# M2_NVME.net
KiCad netlist of a schematic drawn in Altium Designer
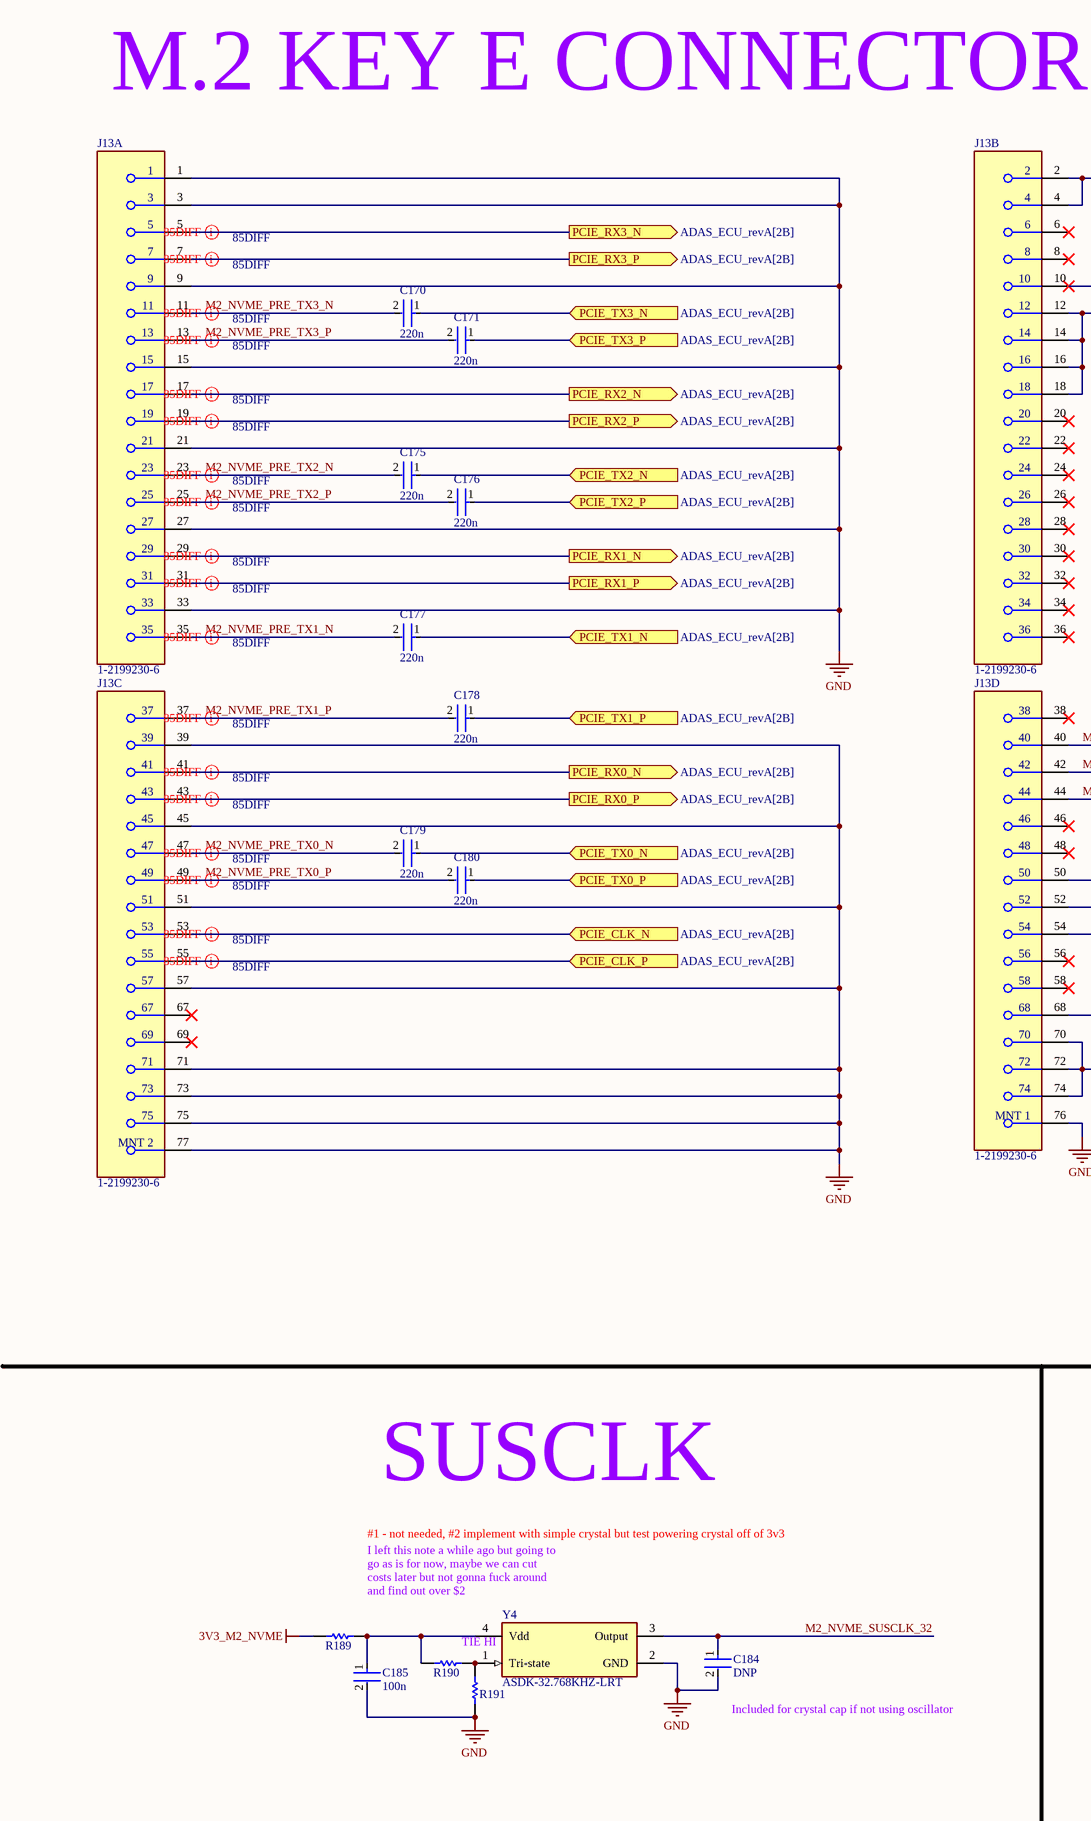
[diagram p0: M2_NVME.SchDoc, left]
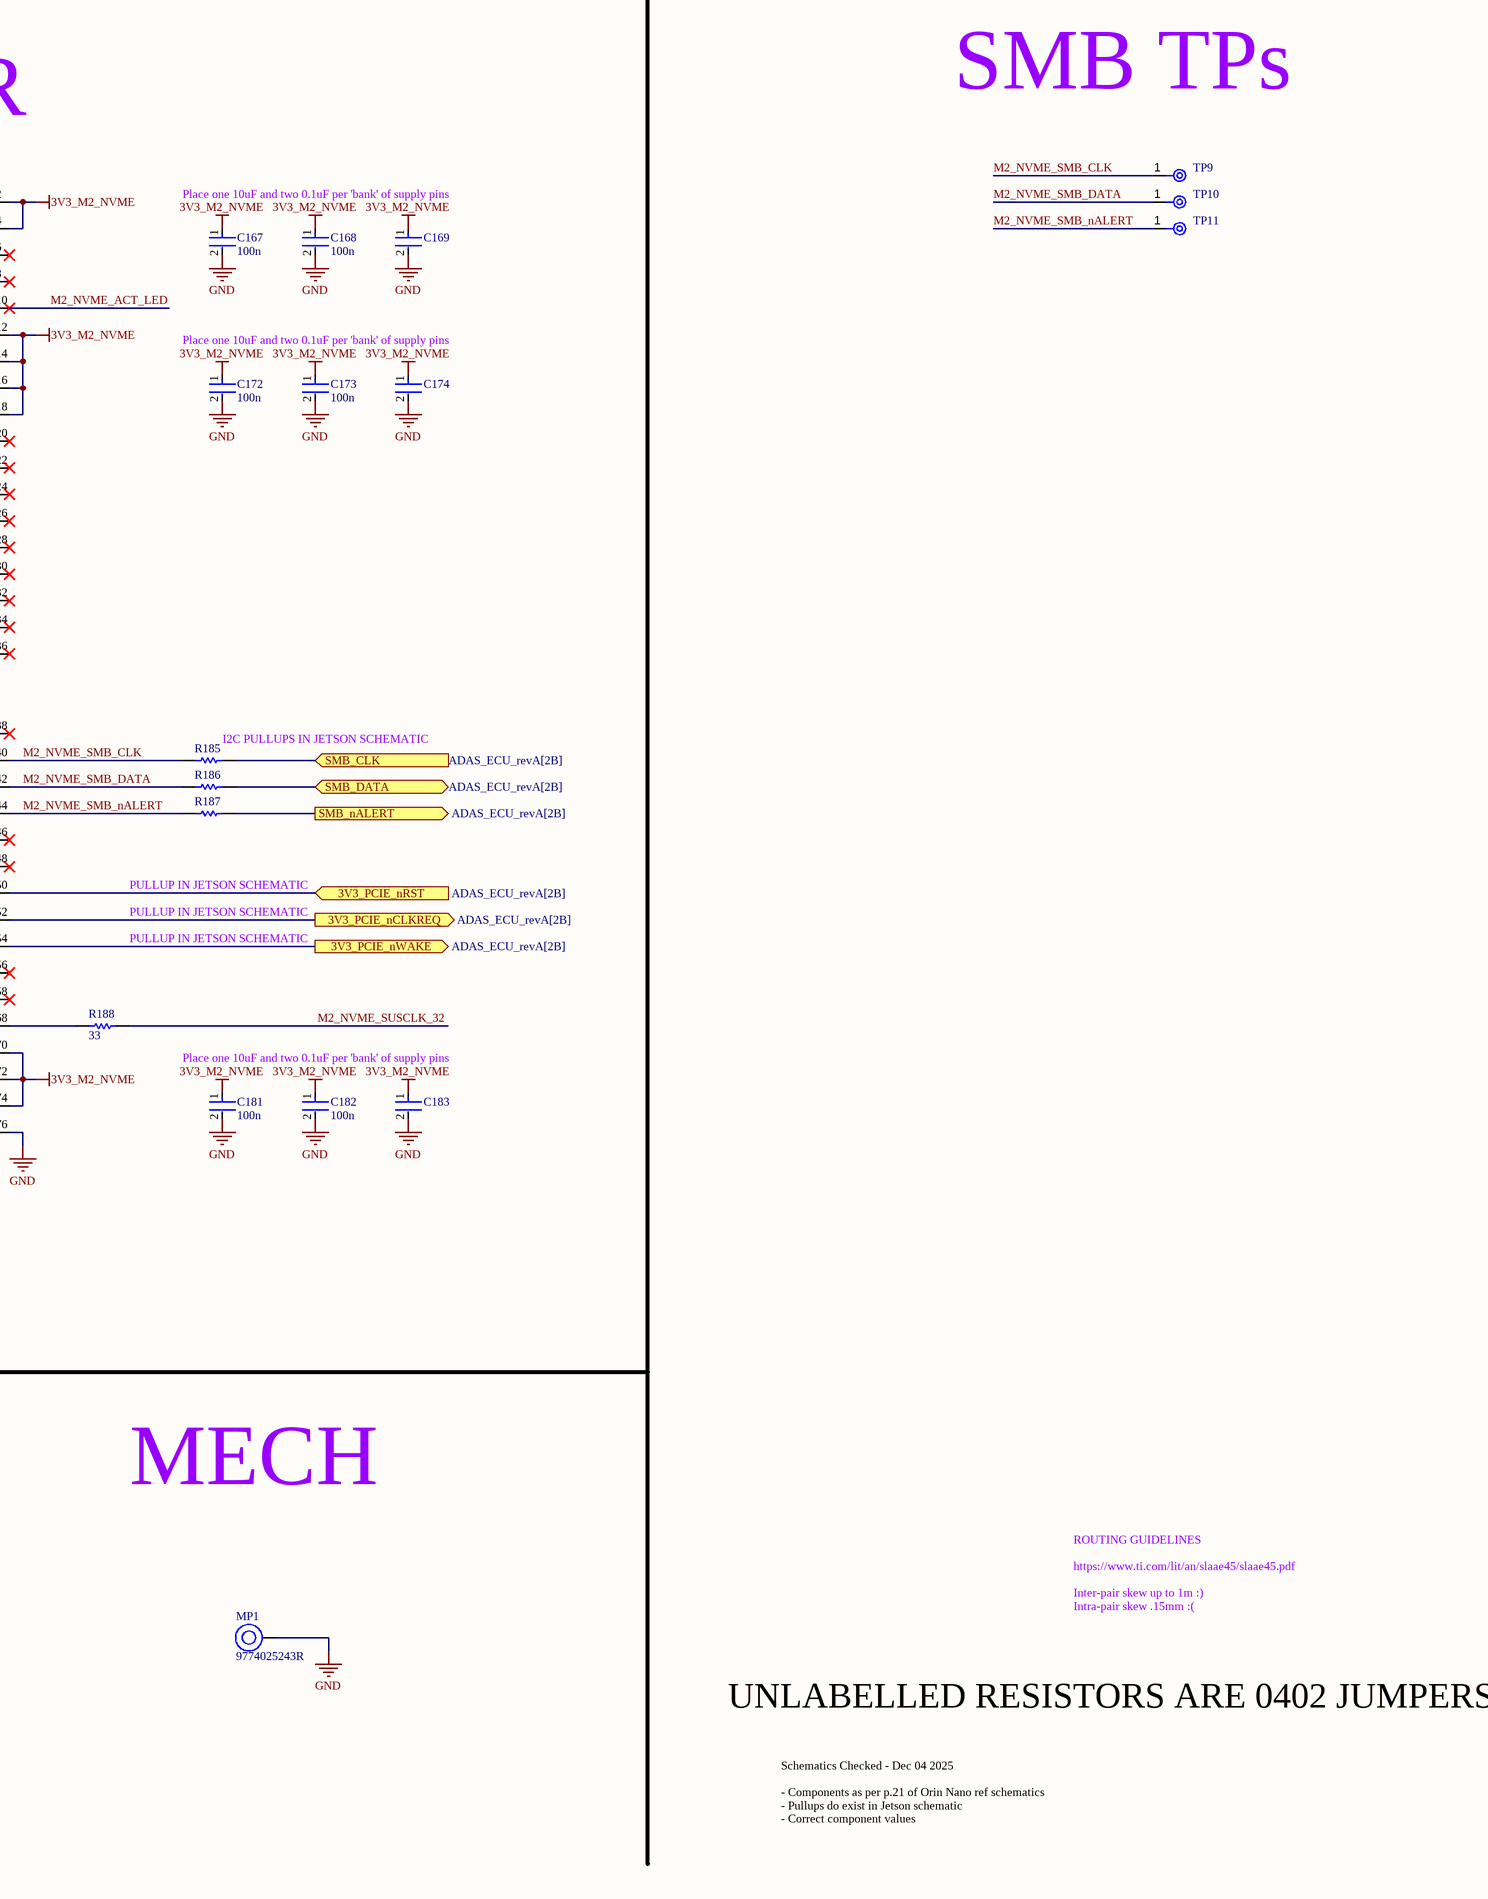
[diagram p1: M2_NVME.SchDoc, right]

(export (version "E")
  (design (tool "Eeschema 10.0.6"))
  (components
    (comp (ref "C167")
      (value "100n")
      (footprint "FP-0402-L_1_0_0_05-W_0_5-IPC_A")
      (description "LARGE PADS, 0402 CAP, CHANGE COMMENT TO MATCH REAL P/N")
      (libsource (lib "Space Concordia") (part "b4654b650e69147ec39a6b967a45e02"))
    )
    (comp (ref "C168")
      (value "100n")
      (footprint "FP-0402-L_1_0_0_05-W_0_5-IPC_A")
      (description "LARGE PADS, 0402 CAP, CHANGE COMMENT TO MATCH REAL P/N")
      (libsource (lib "Space Concordia") (part "b4654b650e69147ec39a6b967a45e02"))
    )
    (comp (ref "C169")
      (value "GRM188R60J106ME47D")
      (footprint "FP-GRM188-0_1-e0_2_0_55-IPC_A")
      (description "Chip Multilayer Ceramic Capacitors for General Purpose, 0603, 10uF, X5R, 15%, 20%, 6.3V")
      (fields (field (name "VOLTAGE") "6.3V") (field (name "TOLERANCE") "20%"))
      (libsource (lib "Altium Content Vault") (part "02cd4be3c70576c341d710602a673aa"))
    )
    (comp (ref "C170")
      (value "220n")
      (footprint "FP-0402-L_1_0_0_05-W_0_5-IPC_A")
      (description "LARGE PADS, 0402 CAP, CHANGE COMMENT TO MATCH REAL P/N")
      (libsource (lib "Space Concordia") (part "b4654b650e69147ec39a6b967a45e02"))
    )
    (comp (ref "C171")
      (value "220n")
      (footprint "FP-0402-L_1_0_0_05-W_0_5-IPC_A")
      (description "LARGE PADS, 0402 CAP, CHANGE COMMENT TO MATCH REAL P/N")
      (libsource (lib "Space Concordia") (part "b4654b650e69147ec39a6b967a45e02"))
    )
    (comp (ref "C172")
      (value "100n")
      (footprint "FP-0402-L_1_0_0_05-W_0_5-IPC_A")
      (description "LARGE PADS, 0402 CAP, CHANGE COMMENT TO MATCH REAL P/N")
      (libsource (lib "Space Concordia") (part "b4654b650e69147ec39a6b967a45e02"))
    )
    (comp (ref "C173")
      (value "100n")
      (footprint "FP-0402-L_1_0_0_05-W_0_5-IPC_A")
      (description "LARGE PADS, 0402 CAP, CHANGE COMMENT TO MATCH REAL P/N")
      (libsource (lib "Space Concordia") (part "b4654b650e69147ec39a6b967a45e02"))
    )
    (comp (ref "C174")
      (value "GRM188R60J106ME47D")
      (footprint "FP-GRM188-0_1-e0_2_0_55-IPC_A")
      (description "Chip Multilayer Ceramic Capacitors for General Purpose, 0603, 10uF, X5R, 15%, 20%, 6.3V")
      (fields (field (name "VOLTAGE") "6.3V") (field (name "TOLERANCE") "20%"))
      (libsource (lib "Altium Content Vault") (part "02cd4be3c70576c341d710602a673aa"))
    )
    (comp (ref "C175")
      (value "220n")
      (footprint "FP-0402-L_1_0_0_05-W_0_5-IPC_A")
      (description "LARGE PADS, 0402 CAP, CHANGE COMMENT TO MATCH REAL P/N")
      (libsource (lib "Space Concordia") (part "b4654b650e69147ec39a6b967a45e02"))
    )
    (comp (ref "C176")
      (value "220n")
      (footprint "FP-0402-L_1_0_0_05-W_0_5-IPC_A")
      (description "LARGE PADS, 0402 CAP, CHANGE COMMENT TO MATCH REAL P/N")
      (libsource (lib "Space Concordia") (part "b4654b650e69147ec39a6b967a45e02"))
    )
    (comp (ref "C177")
      (value "220n")
      (footprint "FP-0402-L_1_0_0_05-W_0_5-IPC_A")
      (description "LARGE PADS, 0402 CAP, CHANGE COMMENT TO MATCH REAL P/N")
      (libsource (lib "Space Concordia") (part "b4654b650e69147ec39a6b967a45e02"))
    )
    (comp (ref "C178")
      (value "220n")
      (footprint "FP-0402-L_1_0_0_05-W_0_5-IPC_A")
      (description "LARGE PADS, 0402 CAP, CHANGE COMMENT TO MATCH REAL P/N")
      (libsource (lib "Space Concordia") (part "b4654b650e69147ec39a6b967a45e02"))
    )
    (comp (ref "C179")
      (value "220n")
      (footprint "FP-0402-L_1_0_0_05-W_0_5-IPC_A")
      (description "LARGE PADS, 0402 CAP, CHANGE COMMENT TO MATCH REAL P/N")
      (libsource (lib "Space Concordia") (part "b4654b650e69147ec39a6b967a45e02"))
    )
    (comp (ref "C180")
      (value "220n")
      (footprint "FP-0402-L_1_0_0_05-W_0_5-IPC_A")
      (description "LARGE PADS, 0402 CAP, CHANGE COMMENT TO MATCH REAL P/N")
      (libsource (lib "Space Concordia") (part "b4654b650e69147ec39a6b967a45e02"))
    )
    (comp (ref "C181")
      (value "100n")
      (footprint "FP-0402-L_1_0_0_05-W_0_5-IPC_A")
      (description "LARGE PADS, 0402 CAP, CHANGE COMMENT TO MATCH REAL P/N")
      (libsource (lib "Space Concordia") (part "b4654b650e69147ec39a6b967a45e02"))
    )
    (comp (ref "C182")
      (value "100n")
      (footprint "FP-0402-L_1_0_0_05-W_0_5-IPC_A")
      (description "LARGE PADS, 0402 CAP, CHANGE COMMENT TO MATCH REAL P/N")
      (libsource (lib "Space Concordia") (part "b4654b650e69147ec39a6b967a45e02"))
    )
    (comp (ref "C183")
      (value "GRM188R60J106ME47D")
      (footprint "FP-GRM188-0_1-e0_2_0_55-IPC_A")
      (description "Chip Multilayer Ceramic Capacitors for General Purpose, 0603, 10uF, X5R, 15%, 20%, 6.3V")
      (fields (field (name "VOLTAGE") "6.3V") (field (name "TOLERANCE") "20%"))
      (libsource (lib "Altium Content Vault") (part "02cd4be3c70576c341d710602a673aa"))
    )
    (comp (ref "C184")
      (value "DNP")
      (footprint "FP-0402-L_1_0_0_05-W_0_5-IPC_A")
      (description "LARGE PADS, 0402 CAP, CHANGE COMMENT TO MATCH REAL P/N")
      (libsource (lib "Space Concordia") (part "b4654b650e69147ec39a6b967a45e02"))
    )
    (comp (ref "C185")
      (value "100n")
      (footprint "FP-0402-L_1_0_0_05-W_0_5-IPC_A")
      (description "LARGE PADS, 0402 CAP, CHANGE COMMENT TO MATCH REAL P/N")
      (libsource (lib "Space Concordia") (part "b4654b650e69147ec39a6b967a45e02"))
    )
    (comp (ref "J13")
      (value "1-2199230-6")
      (footprint "FP-1-2199230-6-MFG")
      (description "CONN EDGE DUAL FMALE 67POS 0.020")
      (fields
        (field (name "MANUFACTURER") "TE")
        (field (name "OCTOPART") "https://octopart.com/1-2199230-6-te+connectivity-34969376")
      )
      (libsource (lib "Altium Content Vault") (part "bdc5cd39fb5e3adfc3cf7d042564072"))
    )
    (comp (ref "MP1")
      (value "9774025243R")
      (footprint "9774025243")
      (description "9774025243R Spacer Material: Steel, Tin-Plated Mounting: SMT Series: WA-SMST Thread D: M2")
      (libsource (lib "Altium Content Vault") (part "Spacer"))
    )
    (comp (ref "R185")
      (value "DNP")
      (footprint "RESC1005X40X25ML05T05")
      (description "READ THE NAME")
      (libsource (lib "Space Concordia") (part "CMP-009-00206-2"))
    )
    (comp (ref "R186")
      (value "DNP")
      (footprint "RESC1005X40X25ML05T05")
      (description "READ THE NAME")
      (libsource (lib "Space Concordia") (part "CMP-009-00206-2"))
    )
    (comp (ref "R187")
      (value "DNP")
      (footprint "RESC1005X40X25ML05T05")
      (description "READ THE NAME")
      (libsource (lib "Space Concordia") (part "CMP-009-00206-2"))
    )
    (comp (ref "R188")
      (value "33")
      (footprint "R0603B")
      (description "Resistor")
      (libsource (lib "Space Concordia") (part "Resistor"))
    )
    (comp (ref "R189")
      (value "0402 JUMPER")
      (footprint "RESC1005X40X25ML05T05")
      (description "READ THE NAME")
      (libsource (lib "Space Concordia") (part "CMP-009-00206-2"))
    )
    (comp (ref "R190")
      (value "0402 JUMPER")
      (footprint "RESC1005X40X25ML05T05")
      (description "READ THE NAME")
      (libsource (lib "Space Concordia") (part "CMP-009-00206-2"))
    )
    (comp (ref "R191")
      (value "DNP")
      (footprint "RESC1005X40X25ML05T05")
      (description "READ THE NAME")
      (libsource (lib "Space Concordia") (part "CMP-009-00206-2"))
    )
    (comp (ref "TP9")
      (value "TPAD6R")
      (footprint "New footprint 1")
      (description "Test Point .6mm")
      (libsource (lib "Space Concordia") (part "TP"))
    )
    (comp (ref "TP10")
      (value "TPAD6R")
      (footprint "New footprint 1")
      (description "Test Point .6mm")
      (libsource (lib "Space Concordia") (part "TP"))
    )
    (comp (ref "TP11")
      (value "TPAD6R")
      (footprint "New footprint 1")
      (description "Test Point .6mm")
      (libsource (lib "Space Concordia") (part "TP"))
    )
    (comp (ref "Y4")
      (value "ASDK-32.768KHZ-LRT")
      (footprint "FP-ASDK-MFG")
      (description "XTAL OSC XO 32.7680KHZ CMOS SMD")
      (libsource (lib "Altium Content Vault") (part "a7425352bb6ebc83bfd0f12a23808e7"))
    )
  )
  (nets
    (net (code "1") (name "/3V3_PCIE_nCLKREQ") (class "Default")
      (node (ref "J13") (pin "52") (pinfunction "52_52") (pintype "passive"))
    )
    (net (code "2") (name "/3V3_PCIE_nRST") (class "Default")
      (node (ref "J13") (pin "50") (pinfunction "50_50") (pintype "passive"))
    )
    (net (code "3") (name "/3V3_PCIE_nWAKE") (class "Default")
      (node (ref "J13") (pin "54") (pinfunction "54_54") (pintype "passive"))
    )
    (net (code "4") (name "/M2_NVME_ACT_LED") (class "Default")
      (node (ref "J13") (pin "10") (pinfunction "10_10") (pintype "passive+no_connect"))
    )
    (net (code "5") (name "/M2_NVME_PRE_TX0_N") (class "Default")
      (node (ref "C179") (pin "2") (pinfunction "2_2") (pintype "passive"))
      (node (ref "J13") (pin "47") (pinfunction "47_47") (pintype "passive"))
    )
    (net (code "6") (name "/M2_NVME_PRE_TX0_P") (class "Default")
      (node (ref "C180") (pin "2") (pinfunction "2_2") (pintype "passive"))
      (node (ref "J13") (pin "49") (pinfunction "49_49") (pintype "passive"))
    )
    (net (code "7") (name "/M2_NVME_PRE_TX1_N") (class "Default")
      (node (ref "C177") (pin "2") (pinfunction "2_2") (pintype "passive"))
      (node (ref "J13") (pin "35") (pinfunction "35_35") (pintype "passive"))
    )
    (net (code "8") (name "/M2_NVME_PRE_TX1_P") (class "Default")
      (node (ref "C178") (pin "2") (pinfunction "2_2") (pintype "passive"))
      (node (ref "J13") (pin "37") (pinfunction "37_37") (pintype "passive"))
    )
    (net (code "9") (name "/M2_NVME_PRE_TX2_N") (class "Default")
      (node (ref "C175") (pin "2") (pinfunction "2_2") (pintype "passive"))
      (node (ref "J13") (pin "23") (pinfunction "23_23") (pintype "passive"))
    )
    (net (code "10") (name "/M2_NVME_PRE_TX2_P") (class "Default")
      (node (ref "C176") (pin "2") (pinfunction "2_2") (pintype "passive"))
      (node (ref "J13") (pin "25") (pinfunction "25_25") (pintype "passive"))
    )
    (net (code "11") (name "/M2_NVME_PRE_TX3_N") (class "Default")
      (node (ref "C170") (pin "2") (pinfunction "2_2") (pintype "passive"))
      (node (ref "J13") (pin "11") (pinfunction "11_11") (pintype "passive"))
    )
    (net (code "12") (name "/M2_NVME_PRE_TX3_P") (class "Default")
      (node (ref "C171") (pin "2") (pinfunction "2_2") (pintype "passive"))
      (node (ref "J13") (pin "13") (pinfunction "13_13") (pintype "passive"))
    )
    (net (code "13") (name "/M2_NVME_SMB_CLK") (class "Default")
      (node (ref "J13") (pin "40") (pinfunction "40_40") (pintype "passive"))
      (node (ref "R185") (pin "1") (pinfunction "1_1") (pintype "passive"))
      (node (ref "TP9") (pin "1") (pinfunction "TP_1") (pintype "passive"))
    )
    (net (code "14") (name "/M2_NVME_SMB_DATA") (class "Default")
      (node (ref "J13") (pin "42") (pinfunction "42_42") (pintype "passive"))
      (node (ref "R186") (pin "1") (pinfunction "1_1") (pintype "passive"))
      (node (ref "TP10") (pin "1") (pinfunction "TP_1") (pintype "passive"))
    )
    (net (code "15") (name "/M2_NVME_SMB_nALERT") (class "Default")
      (node (ref "J13") (pin "44") (pinfunction "44_44") (pintype "passive"))
      (node (ref "R187") (pin "1") (pinfunction "1_1") (pintype "passive"))
      (node (ref "TP11") (pin "1") (pinfunction "TP_1") (pintype "passive"))
    )
    (net (code "16") (name "/M2_NVME_SUSCLK_32") (class "Default")
      (node (ref "C184") (pin "1") (pinfunction "1_1") (pintype "passive"))
      (node (ref "R188") (pin "1") (pinfunction "1_1") (pintype "passive"))
      (node (ref "Y4") (pin "3") (pinfunction "Output_3") (pintype "tri_state"))
    )
    (net (code "17") (name "/PCIE_CLK_N") (class "Default")
      (node (ref "J13") (pin "53") (pinfunction "53_53") (pintype "passive"))
    )
    (net (code "18") (name "/PCIE_CLK_P") (class "Default")
      (node (ref "J13") (pin "55") (pinfunction "55_55") (pintype "passive"))
    )
    (net (code "19") (name "/PCIE_RX0_N") (class "Default")
      (node (ref "J13") (pin "41") (pinfunction "41_41") (pintype "passive"))
    )
    (net (code "20") (name "/PCIE_RX0_P") (class "Default")
      (node (ref "J13") (pin "43") (pinfunction "43_43") (pintype "passive"))
    )
    (net (code "21") (name "/PCIE_RX1_N") (class "Default")
      (node (ref "J13") (pin "29") (pinfunction "29_29") (pintype "passive"))
    )
    (net (code "22") (name "/PCIE_RX1_P") (class "Default")
      (node (ref "J13") (pin "31") (pinfunction "31_31") (pintype "passive"))
    )
    (net (code "23") (name "/PCIE_RX2_N") (class "Default")
      (node (ref "J13") (pin "17") (pinfunction "17_17") (pintype "passive"))
    )
    (net (code "24") (name "/PCIE_RX2_P") (class "Default")
      (node (ref "J13") (pin "19") (pinfunction "19_19") (pintype "passive"))
    )
    (net (code "25") (name "/PCIE_RX3_N") (class "Default")
      (node (ref "J13") (pin "5") (pinfunction "5_5") (pintype "passive"))
    )
    (net (code "26") (name "/PCIE_RX3_P") (class "Default")
      (node (ref "J13") (pin "7") (pinfunction "7_7") (pintype "passive"))
    )
    (net (code "27") (name "/PCIE_TX0_N") (class "Default")
      (node (ref "C179") (pin "1") (pinfunction "1_1") (pintype "passive"))
    )
    (net (code "28") (name "/PCIE_TX0_P") (class "Default")
      (node (ref "C180") (pin "1") (pinfunction "1_1") (pintype "passive"))
    )
    (net (code "29") (name "/PCIE_TX1_N") (class "Default")
      (node (ref "C177") (pin "1") (pinfunction "1_1") (pintype "passive"))
    )
    (net (code "30") (name "/PCIE_TX1_P") (class "Default")
      (node (ref "C178") (pin "1") (pinfunction "1_1") (pintype "passive"))
    )
    (net (code "31") (name "/PCIE_TX2_N") (class "Default")
      (node (ref "C175") (pin "1") (pinfunction "1_1") (pintype "passive"))
    )
    (net (code "32") (name "/PCIE_TX2_P") (class "Default")
      (node (ref "C176") (pin "1") (pinfunction "1_1") (pintype "passive"))
    )
    (net (code "33") (name "/PCIE_TX3_N") (class "Default")
      (node (ref "C170") (pin "1") (pinfunction "1_1") (pintype "passive"))
    )
    (net (code "34") (name "/PCIE_TX3_P") (class "Default")
      (node (ref "C171") (pin "1") (pinfunction "1_1") (pintype "passive"))
    )
    (net (code "35") (name "/SMB_CLK") (class "Default")
      (node (ref "R185") (pin "2") (pinfunction "2_2") (pintype "passive"))
    )
    (net (code "36") (name "/SMB_DATA") (class "Default")
      (node (ref "R186") (pin "2") (pinfunction "2_2") (pintype "passive"))
    )
    (net (code "37") (name "/SMB_nALERT") (class "Default")
      (node (ref "R187") (pin "2") (pinfunction "2_2") (pintype "passive"))
    )
    (net (code "38") (name "3V3_M2_NVME") (class "Default")
      (node (ref "C167") (pin "1") (pinfunction "1_1") (pintype "passive"))
      (node (ref "C168") (pin "1") (pinfunction "1_1") (pintype "passive"))
      (node (ref "C169") (pin "1") (pinfunction "1_1") (pintype "passive"))
      (node (ref "C172") (pin "1") (pinfunction "1_1") (pintype "passive"))
      (node (ref "C173") (pin "1") (pinfunction "1_1") (pintype "passive"))
      (node (ref "C174") (pin "1") (pinfunction "1_1") (pintype "passive"))
      (node (ref "C181") (pin "1") (pinfunction "1_1") (pintype "passive"))
      (node (ref "C182") (pin "1") (pinfunction "1_1") (pintype "passive"))
      (node (ref "C183") (pin "1") (pinfunction "1_1") (pintype "passive"))
      (node (ref "J13") (pin "12") (pinfunction "12_12") (pintype "passive"))
      (node (ref "J13") (pin "14") (pinfunction "14_14") (pintype "passive"))
      (node (ref "J13") (pin "16") (pinfunction "16_16") (pintype "passive"))
      (node (ref "J13") (pin "18") (pinfunction "18_18") (pintype "passive"))
      (node (ref "J13") (pin "2") (pinfunction "2_2") (pintype "passive"))
      (node (ref "J13") (pin "4") (pinfunction "4_4") (pintype "passive"))
      (node (ref "J13") (pin "70") (pinfunction "70_70") (pintype "passive"))
      (node (ref "J13") (pin "72") (pinfunction "72_72") (pintype "passive"))
      (node (ref "J13") (pin "74") (pinfunction "74_74") (pintype "passive"))
      (node (ref "R189") (pin "1") (pinfunction "1_1") (pintype "passive"))
    )
    (net (code "39") (name "GND") (class "Default")
      (node (ref "C167") (pin "2") (pinfunction "2_2") (pintype "passive"))
      (node (ref "C168") (pin "2") (pinfunction "2_2") (pintype "passive"))
      (node (ref "C169") (pin "2") (pinfunction "2_2") (pintype "passive"))
      (node (ref "C172") (pin "2") (pinfunction "2_2") (pintype "passive"))
      (node (ref "C173") (pin "2") (pinfunction "2_2") (pintype "passive"))
      (node (ref "C174") (pin "2") (pinfunction "2_2") (pintype "passive"))
      (node (ref "C181") (pin "2") (pinfunction "2_2") (pintype "passive"))
      (node (ref "C182") (pin "2") (pinfunction "2_2") (pintype "passive"))
      (node (ref "C183") (pin "2") (pinfunction "2_2") (pintype "passive"))
      (node (ref "C184") (pin "2") (pinfunction "2_2") (pintype "passive"))
      (node (ref "C185") (pin "2") (pinfunction "2_2") (pintype "passive"))
      (node (ref "J13") (pin "1") (pinfunction "1_1") (pintype "passive"))
      (node (ref "J13") (pin "15") (pinfunction "15_15") (pintype "passive"))
      (node (ref "J13") (pin "21") (pinfunction "21_21") (pintype "passive"))
      (node (ref "J13") (pin "27") (pinfunction "27_27") (pintype "passive"))
      (node (ref "J13") (pin "3") (pinfunction "3_3") (pintype "passive"))
      (node (ref "J13") (pin "33") (pinfunction "33_33") (pintype "passive"))
      (node (ref "J13") (pin "39") (pinfunction "39_39") (pintype "passive"))
      (node (ref "J13") (pin "45") (pinfunction "45_45") (pintype "passive"))
      (node (ref "J13") (pin "51") (pinfunction "51_51") (pintype "passive"))
      (node (ref "J13") (pin "57") (pinfunction "57_57") (pintype "passive"))
      (node (ref "J13") (pin "71") (pinfunction "71_71") (pintype "passive"))
      (node (ref "J13") (pin "73") (pinfunction "73_73") (pintype "passive"))
      (node (ref "J13") (pin "75") (pinfunction "75_75") (pintype "passive"))
      (node (ref "J13") (pin "76") (pinfunction "MNT_1_76") (pintype "passive"))
      (node (ref "J13") (pin "77") (pinfunction "MNT_2_77") (pintype "passive"))
      (node (ref "J13") (pin "9") (pinfunction "9_9") (pintype "passive"))
      (node (ref "MP1") (pin "1") (pinfunction "1_1") (pintype "passive"))
      (node (ref "R191") (pin "1") (pinfunction "1_1") (pintype "passive"))
      (node (ref "Y4") (pin "2") (pinfunction "GND_2") (pintype "power_in"))
    )
    (net (code "40") (name "Net-(J13-Pad68)") (class "Default")
      (node (ref "J13") (pin "68") (pinfunction "68_68") (pintype "passive"))
      (node (ref "R188") (pin "2") (pinfunction "2_2") (pintype "passive"))
    )
    (net (code "41") (name "Net-(Y4-Tri-state)") (class "Default")
      (node (ref "R190") (pin "2") (pinfunction "2_2") (pintype "passive"))
      (node (ref "R191") (pin "2") (pinfunction "2_2") (pintype "passive"))
      (node (ref "Y4") (pin "1") (pinfunction "Tri-state_1") (pintype "input"))
    )
    (net (code "42") (name "Net-(Y4-Vdd)") (class "Default")
      (node (ref "C185") (pin "1") (pinfunction "1_1") (pintype "passive"))
      (node (ref "R189") (pin "2") (pinfunction "2_2") (pintype "passive"))
      (node (ref "R190") (pin "1") (pinfunction "1_1") (pintype "passive"))
      (node (ref "Y4") (pin "4") (pinfunction "Vdd_4") (pintype "power_in"))
    )
    (net (code "43") (name "unconnected-(J13-Pad6)") (class "Default")
      (node (ref "J13") (pin "6") (pinfunction "6_6") (pintype "passive+no_connect"))
    )
    (net (code "44") (name "unconnected-(J13-Pad8)") (class "Default")
      (node (ref "J13") (pin "8") (pinfunction "8_8") (pintype "passive+no_connect"))
    )
    (net (code "45") (name "unconnected-(J13-Pad20)") (class "Default")
      (node (ref "J13") (pin "20") (pinfunction "20_20") (pintype "passive+no_connect"))
    )
    (net (code "46") (name "unconnected-(J13-Pad22)") (class "Default")
      (node (ref "J13") (pin "22") (pinfunction "22_22") (pintype "passive+no_connect"))
    )
    (net (code "47") (name "unconnected-(J13-Pad24)") (class "Default")
      (node (ref "J13") (pin "24") (pinfunction "24_24") (pintype "passive+no_connect"))
    )
    (net (code "48") (name "unconnected-(J13-Pad26)") (class "Default")
      (node (ref "J13") (pin "26") (pinfunction "26_26") (pintype "passive+no_connect"))
    )
    (net (code "49") (name "unconnected-(J13-Pad28)") (class "Default")
      (node (ref "J13") (pin "28") (pinfunction "28_28") (pintype "passive+no_connect"))
    )
    (net (code "50") (name "unconnected-(J13-Pad30)") (class "Default")
      (node (ref "J13") (pin "30") (pinfunction "30_30") (pintype "passive+no_connect"))
    )
    (net (code "51") (name "unconnected-(J13-Pad32)") (class "Default")
      (node (ref "J13") (pin "32") (pinfunction "32_32") (pintype "passive+no_connect"))
    )
    (net (code "52") (name "unconnected-(J13-Pad34)") (class "Default")
      (node (ref "J13") (pin "34") (pinfunction "34_34") (pintype "passive+no_connect"))
    )
    (net (code "53") (name "unconnected-(J13-Pad36)") (class "Default")
      (node (ref "J13") (pin "36") (pinfunction "36_36") (pintype "passive+no_connect"))
    )
    (net (code "54") (name "unconnected-(J13-Pad38)") (class "Default")
      (node (ref "J13") (pin "38") (pinfunction "38_38") (pintype "passive+no_connect"))
    )
    (net (code "55") (name "unconnected-(J13-Pad46)") (class "Default")
      (node (ref "J13") (pin "46") (pinfunction "46_46") (pintype "passive+no_connect"))
    )
    (net (code "56") (name "unconnected-(J13-Pad48)") (class "Default")
      (node (ref "J13") (pin "48") (pinfunction "48_48") (pintype "passive+no_connect"))
    )
    (net (code "57") (name "unconnected-(J13-Pad56)") (class "Default")
      (node (ref "J13") (pin "56") (pinfunction "56_56") (pintype "passive+no_connect"))
    )
    (net (code "58") (name "unconnected-(J13-Pad58)") (class "Default")
      (node (ref "J13") (pin "58") (pinfunction "58_58") (pintype "passive+no_connect"))
    )
    (net (code "59") (name "unconnected-(J13-Pad67)") (class "Default")
      (node (ref "J13") (pin "67") (pinfunction "67_67") (pintype "passive+no_connect"))
    )
    (net (code "60") (name "unconnected-(J13-Pad69)") (class "Default")
      (node (ref "J13") (pin "69") (pinfunction "69_69") (pintype "passive+no_connect"))
    )
  )
)
